# SCH_PianoBoard_P1_2024-09-13.net
KiCad netlist of a schematic drawn in EasyEDA
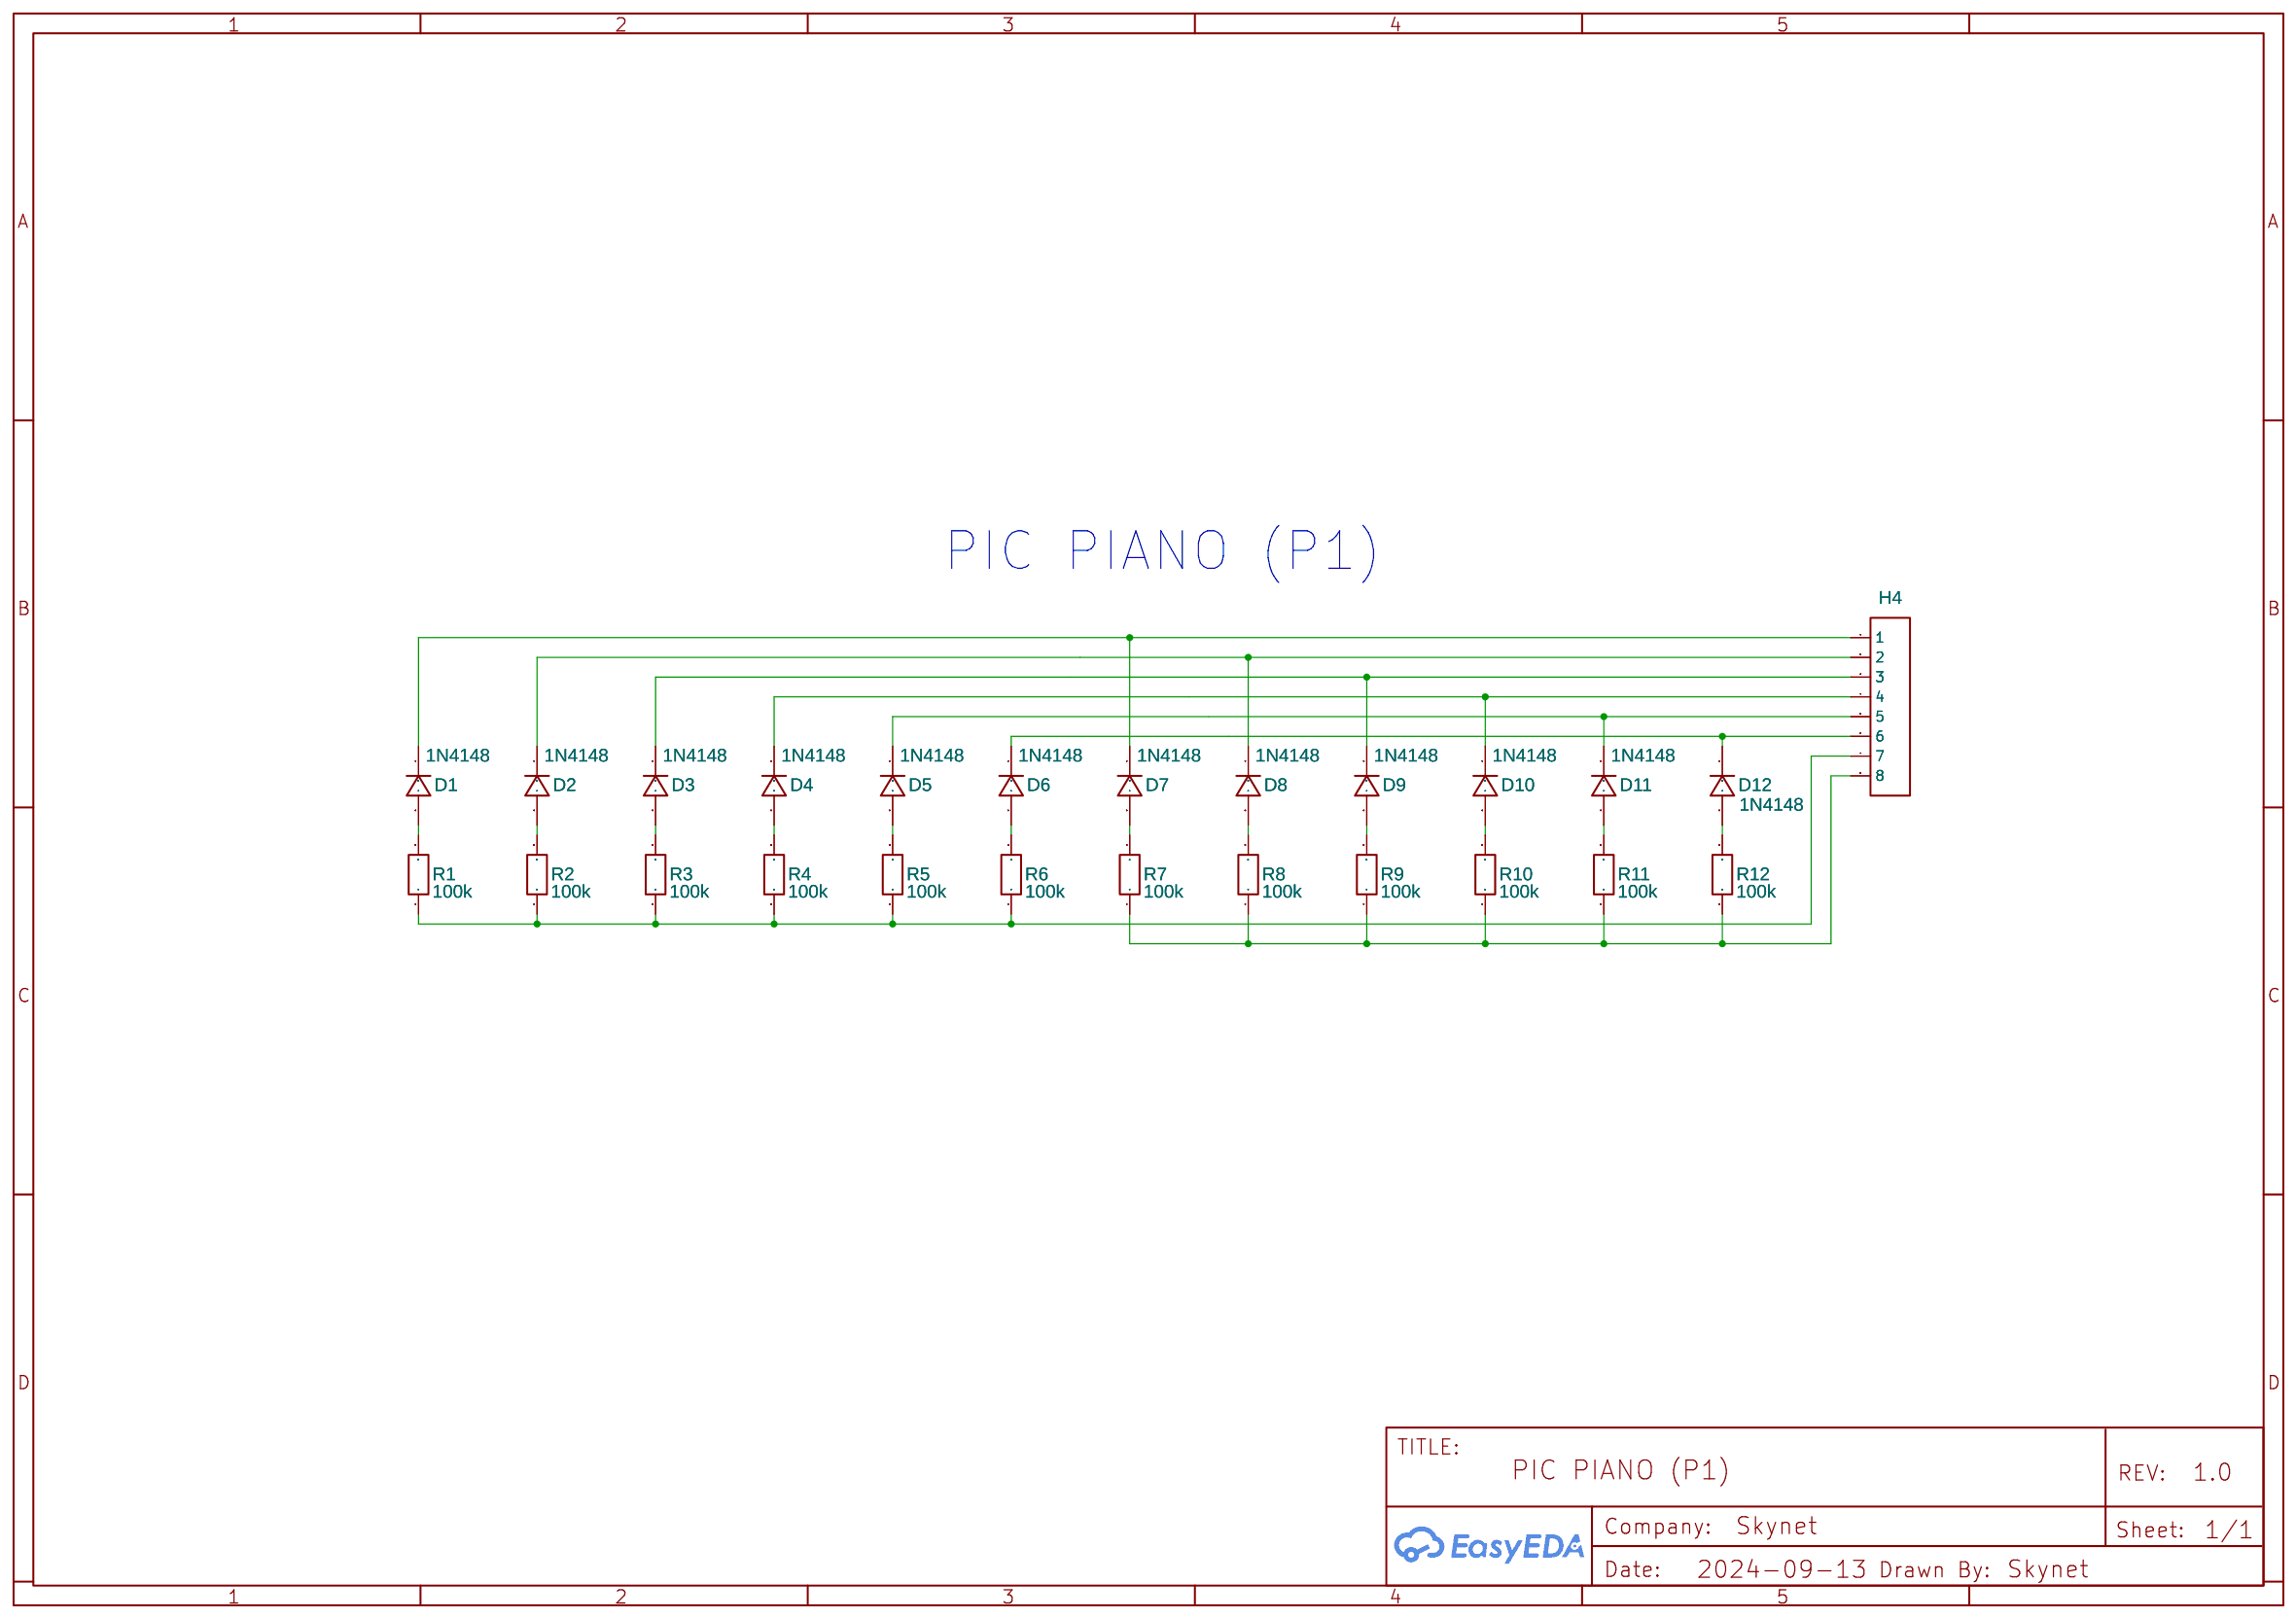
[diagram p0: schematic sheet]

(export (version "E")
  (design (tool "Eeschema 10.0.6"))
  (components
    (comp (ref "D1")
      (value "1N4148")
      (fields (field (name "Manufacturer Part") "1N4148WX-TP") (field (name "Manufacturer") "MCC(美微科)"))
      (libsource (lib "") (part "1N4148WX-TP"))
    )
    (comp (ref "D2")
      (value "1N4148")
      (fields (field (name "Manufacturer Part") "1N4148WX-TP") (field (name "Manufacturer") "MCC(美微科)"))
      (libsource (lib "") (part "1N4148WX-TP"))
    )
    (comp (ref "D3")
      (value "1N4148")
      (fields (field (name "Manufacturer Part") "1N4148WX-TP") (field (name "Manufacturer") "MCC(美微科)"))
      (libsource (lib "") (part "1N4148WX-TP"))
    )
    (comp (ref "D4")
      (value "1N4148")
      (fields (field (name "Manufacturer Part") "1N4148WX-TP") (field (name "Manufacturer") "MCC(美微科)"))
      (libsource (lib "") (part "1N4148WX-TP"))
    )
    (comp (ref "D5")
      (value "1N4148")
      (fields (field (name "Manufacturer Part") "1N4148WX-TP") (field (name "Manufacturer") "MCC(美微科)"))
      (libsource (lib "") (part "1N4148WX-TP"))
    )
    (comp (ref "D6")
      (value "1N4148")
      (fields (field (name "Manufacturer Part") "1N4148WX-TP") (field (name "Manufacturer") "MCC(美微科)"))
      (libsource (lib "") (part "1N4148WX-TP"))
    )
    (comp (ref "D7")
      (value "1N4148")
      (fields (field (name "Manufacturer Part") "1N4148WX-TP") (field (name "Manufacturer") "MCC(美微科)"))
      (libsource (lib "") (part "1N4148WX-TP"))
    )
    (comp (ref "D8")
      (value "1N4148")
      (fields (field (name "Manufacturer Part") "1N4148WX-TP") (field (name "Manufacturer") "MCC(美微科)"))
      (libsource (lib "") (part "1N4148WX-TP"))
    )
    (comp (ref "D9")
      (value "1N4148")
      (fields (field (name "Manufacturer Part") "1N4148WX-TP") (field (name "Manufacturer") "MCC(美微科)"))
      (libsource (lib "") (part "1N4148WX-TP"))
    )
    (comp (ref "D10")
      (value "1N4148")
      (fields (field (name "Manufacturer Part") "1N4148WX-TP") (field (name "Manufacturer") "MCC(美微科)"))
      (libsource (lib "") (part "1N4148WX-TP"))
    )
    (comp (ref "D11")
      (value "1N4148")
      (fields (field (name "Manufacturer Part") "1N4148WX-TP") (field (name "Manufacturer") "MCC(美微科)"))
      (libsource (lib "") (part "1N4148WX-TP"))
    )
    (comp (ref "D12")
      (value "1N4148")
      (fields (field (name "Manufacturer Part") "1N4148WX-TP") (field (name "Manufacturer") "MCC(美微科)"))
      (libsource (lib "") (part "1N4148WX-TP"))
    )
    (comp (ref "H4") (value "HDR-F-2.54_1x8") (libsource (lib "") (part "HDR-F-2.54_1x8")))
    (comp (ref "R1") (value "100k") (libsource (lib "") (part "R_0603_EU")))
    (comp (ref "R2") (value "100k") (libsource (lib "") (part "R_0603_EU")))
    (comp (ref "R3") (value "100k") (libsource (lib "") (part "R_0603_EU")))
    (comp (ref "R4") (value "100k") (libsource (lib "") (part "R_0603_EU")))
    (comp (ref "R5") (value "100k") (libsource (lib "") (part "R_0603_EU")))
    (comp (ref "R6") (value "100k") (libsource (lib "") (part "R_0603_EU")))
    (comp (ref "R7") (value "100k") (libsource (lib "") (part "R_0603_EU")))
    (comp (ref "R8") (value "100k") (libsource (lib "") (part "R_0603_EU")))
    (comp (ref "R9") (value "100k") (libsource (lib "") (part "R_0603_EU")))
    (comp (ref "R10") (value "100k") (libsource (lib "") (part "R_0603_EU")))
    (comp (ref "R11") (value "100k") (libsource (lib "") (part "R_0603_EU")))
    (comp (ref "R12") (value "100k") (libsource (lib "") (part "R_0603_EU")))
  )
  (nets
    (net (code "1") (name "Net-(D1-A)") (class "Default")
      (node (ref "D1") (pin "2") (pinfunction "A_2") (pintype "unspecified"))
      (node (ref "R1") (pin "2") (pinfunction "2_2") (pintype "unspecified"))
    )
    (net (code "2") (name "Net-(D1-C)") (class "Default")
      (node (ref "D1") (pin "1") (pinfunction "C_1") (pintype "unspecified"))
      (node (ref "D7") (pin "1") (pinfunction "C_1") (pintype "unspecified"))
      (node (ref "H4") (pin "1") (pinfunction "1_1") (pintype "unspecified"))
    )
    (net (code "3") (name "Net-(D2-A)") (class "Default")
      (node (ref "D2") (pin "2") (pinfunction "A_2") (pintype "unspecified"))
      (node (ref "R2") (pin "2") (pinfunction "2_2") (pintype "unspecified"))
    )
    (net (code "4") (name "Net-(D2-C)") (class "Default")
      (node (ref "D2") (pin "1") (pinfunction "C_1") (pintype "unspecified"))
      (node (ref "D8") (pin "1") (pinfunction "C_1") (pintype "unspecified"))
      (node (ref "H4") (pin "2") (pinfunction "2_2") (pintype "unspecified"))
    )
    (net (code "5") (name "Net-(D3-A)") (class "Default")
      (node (ref "D3") (pin "2") (pinfunction "A_2") (pintype "unspecified"))
      (node (ref "R3") (pin "2") (pinfunction "2_2") (pintype "unspecified"))
    )
    (net (code "6") (name "Net-(D3-C)") (class "Default")
      (node (ref "D3") (pin "1") (pinfunction "C_1") (pintype "unspecified"))
      (node (ref "D9") (pin "1") (pinfunction "C_1") (pintype "unspecified"))
      (node (ref "H4") (pin "3") (pinfunction "3_3") (pintype "unspecified"))
    )
    (net (code "7") (name "Net-(D4-A)") (class "Default")
      (node (ref "D4") (pin "2") (pinfunction "A_2") (pintype "unspecified"))
      (node (ref "R4") (pin "2") (pinfunction "2_2") (pintype "unspecified"))
    )
    (net (code "8") (name "Net-(D5-A)") (class "Default")
      (node (ref "D5") (pin "2") (pinfunction "A_2") (pintype "unspecified"))
      (node (ref "R5") (pin "2") (pinfunction "2_2") (pintype "unspecified"))
    )
    (net (code "9") (name "Net-(D6-A)") (class "Default")
      (node (ref "D6") (pin "2") (pinfunction "A_2") (pintype "unspecified"))
      (node (ref "R6") (pin "2") (pinfunction "2_2") (pintype "unspecified"))
    )
    (net (code "10") (name "Net-(D7-A)") (class "Default")
      (node (ref "D7") (pin "2") (pinfunction "A_2") (pintype "unspecified"))
      (node (ref "R7") (pin "2") (pinfunction "2_2") (pintype "unspecified"))
    )
    (net (code "11") (name "Net-(D8-A)") (class "Default")
      (node (ref "D8") (pin "2") (pinfunction "A_2") (pintype "unspecified"))
      (node (ref "R8") (pin "2") (pinfunction "2_2") (pintype "unspecified"))
    )
    (net (code "12") (name "Net-(D9-A)") (class "Default")
      (node (ref "D9") (pin "2") (pinfunction "A_2") (pintype "unspecified"))
      (node (ref "R9") (pin "2") (pinfunction "2_2") (pintype "unspecified"))
    )
    (net (code "13") (name "Net-(D10-A)") (class "Default")
      (node (ref "D10") (pin "2") (pinfunction "A_2") (pintype "unspecified"))
      (node (ref "R10") (pin "2") (pinfunction "2_2") (pintype "unspecified"))
    )
    (net (code "14") (name "Net-(D10-C)") (class "Default")
      (node (ref "D10") (pin "1") (pinfunction "C_1") (pintype "unspecified"))
      (node (ref "D4") (pin "1") (pinfunction "C_1") (pintype "unspecified"))
      (node (ref "H4") (pin "4") (pinfunction "4_4") (pintype "unspecified"))
    )
    (net (code "15") (name "Net-(D11-A)") (class "Default")
      (node (ref "D11") (pin "2") (pinfunction "A_2") (pintype "unspecified"))
      (node (ref "R11") (pin "2") (pinfunction "2_2") (pintype "unspecified"))
    )
    (net (code "16") (name "Net-(D11-C)") (class "Default")
      (node (ref "D11") (pin "1") (pinfunction "C_1") (pintype "unspecified"))
      (node (ref "D5") (pin "1") (pinfunction "C_1") (pintype "unspecified"))
      (node (ref "H4") (pin "5") (pinfunction "5_5") (pintype "unspecified"))
    )
    (net (code "17") (name "Net-(D12-A)") (class "Default")
      (node (ref "D12") (pin "2") (pinfunction "A_2") (pintype "unspecified"))
      (node (ref "R12") (pin "2") (pinfunction "2_2") (pintype "unspecified"))
    )
    (net (code "18") (name "Net-(D12-C)") (class "Default")
      (node (ref "D12") (pin "1") (pinfunction "C_1") (pintype "unspecified"))
      (node (ref "D6") (pin "1") (pinfunction "C_1") (pintype "unspecified"))
      (node (ref "H4") (pin "6") (pinfunction "6_6") (pintype "unspecified"))
    )
    (net (code "19") (name "Net-(H4-Pad7)") (class "Default")
      (node (ref "H4") (pin "7") (pinfunction "7_7") (pintype "unspecified"))
      (node (ref "R1") (pin "1") (pinfunction "1_1") (pintype "unspecified"))
      (node (ref "R2") (pin "1") (pinfunction "1_1") (pintype "unspecified"))
      (node (ref "R3") (pin "1") (pinfunction "1_1") (pintype "unspecified"))
      (node (ref "R4") (pin "1") (pinfunction "1_1") (pintype "unspecified"))
      (node (ref "R5") (pin "1") (pinfunction "1_1") (pintype "unspecified"))
      (node (ref "R6") (pin "1") (pinfunction "1_1") (pintype "unspecified"))
    )
    (net (code "20") (name "Net-(H4-Pad8)") (class "Default")
      (node (ref "H4") (pin "8") (pinfunction "8_8") (pintype "unspecified"))
      (node (ref "R10") (pin "1") (pinfunction "1_1") (pintype "unspecified"))
      (node (ref "R11") (pin "1") (pinfunction "1_1") (pintype "unspecified"))
      (node (ref "R12") (pin "1") (pinfunction "1_1") (pintype "unspecified"))
      (node (ref "R7") (pin "1") (pinfunction "1_1") (pintype "unspecified"))
      (node (ref "R8") (pin "1") (pinfunction "1_1") (pintype "unspecified"))
      (node (ref "R9") (pin "1") (pinfunction "1_1") (pintype "unspecified"))
    )
  )
)
